# 101_led_yellow.net
KiCad netlist of a schematic drawn in EAGLE
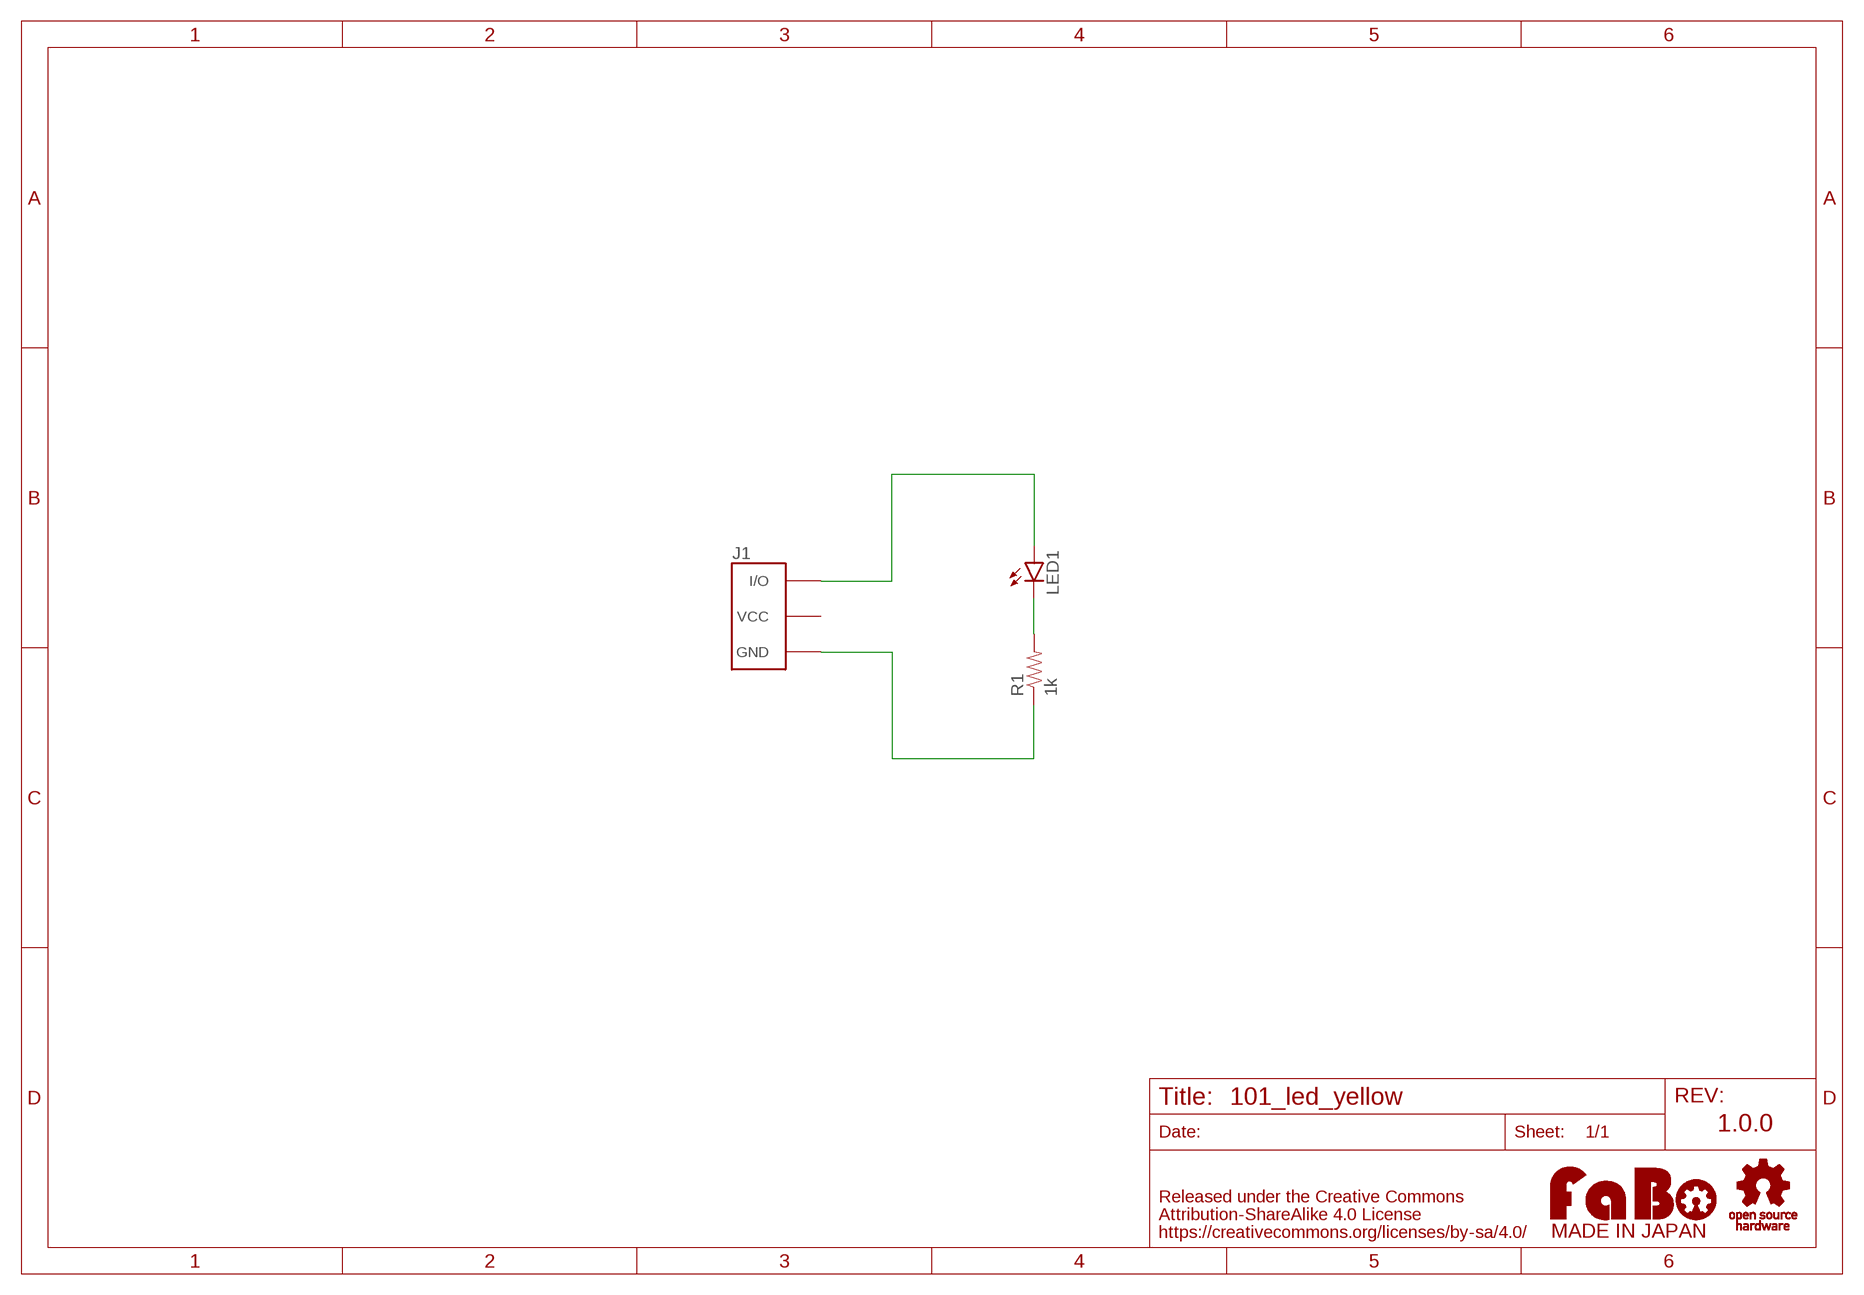
[diagram p0: schematic, sheet 1]

(export (version "E")
  (design (tool "Eeschema 10.0.6"))
  (components
    (comp (ref "J1")
      (value "FABO_BRICK_3PIN")
      (footprint "eagle-import:FABO_BRICK_3PIN")
      (libsource (lib "eagle-import") (part "FABO_BRICK_3PIN"))
    )
    (comp (ref "LED1")
      (value "LED-5MM")
      (footprint "eagle-import:LED-5MM")
      (libsource (lib "eagle-import") (part "LED-5MM"))
    )
    (comp (ref "R1")
      (value "1k")
      (footprint "eagle-import:RES-AXL-REGULAR")
      (libsource (lib "eagle-import") (part "RES-PTH-REGULAR"))
    )
    (comp (ref "U$1")
      (value "LOGO_FABO-M")
      (footprint "eagle-import:LOGO_FABO_M")
      (libsource (lib "eagle-import") (part "LOGO_FABO-M"))
    )
    (comp (ref "U$4")
      (value "LOGO_OSHW_T-M")
      (footprint "eagle-import:LOGO_OSHW_T_M")
      (libsource (lib "eagle-import") (part "LOGO_OSHW_T-M"))
    )
  )
  (nets
    (net (code "1") (name "Net-(J1-I{slash}O)") (class "Default")
      (node (ref "J1") (pin "IN/OUT") (pinfunction "I/O_IN/OUT") (pintype "bidirectional"))
      (node (ref "LED1") (pin "A") (pinfunction "A_A") (pintype "passive"))
    )
    (net (code "2") (name "Net-(LED1-C)") (class "Default")
      (node (ref "LED1") (pin "K") (pinfunction "C_K") (pintype "passive"))
      (node (ref "R1") (pin "P$2") (pinfunction "2_P$2") (pintype "passive"))
    )
    (net (code "3") (name "Net-(R1-1)") (class "Default")
      (node (ref "J1") (pin "GND") (pinfunction "GND_GND") (pintype "bidirectional"))
      (node (ref "R1") (pin "P$1") (pinfunction "1_P$1") (pintype "passive"))
    )
    (net (code "4") (name "unconnected-(J1-PadVCC)") (class "Default")
      (node (ref "J1") (pin "VCC") (pinfunction "VCC_VCC") (pintype "bidirectional"))
    )
  )
)
